# 2023.net
KiCad netlist of a schematic drawn in EAGLE
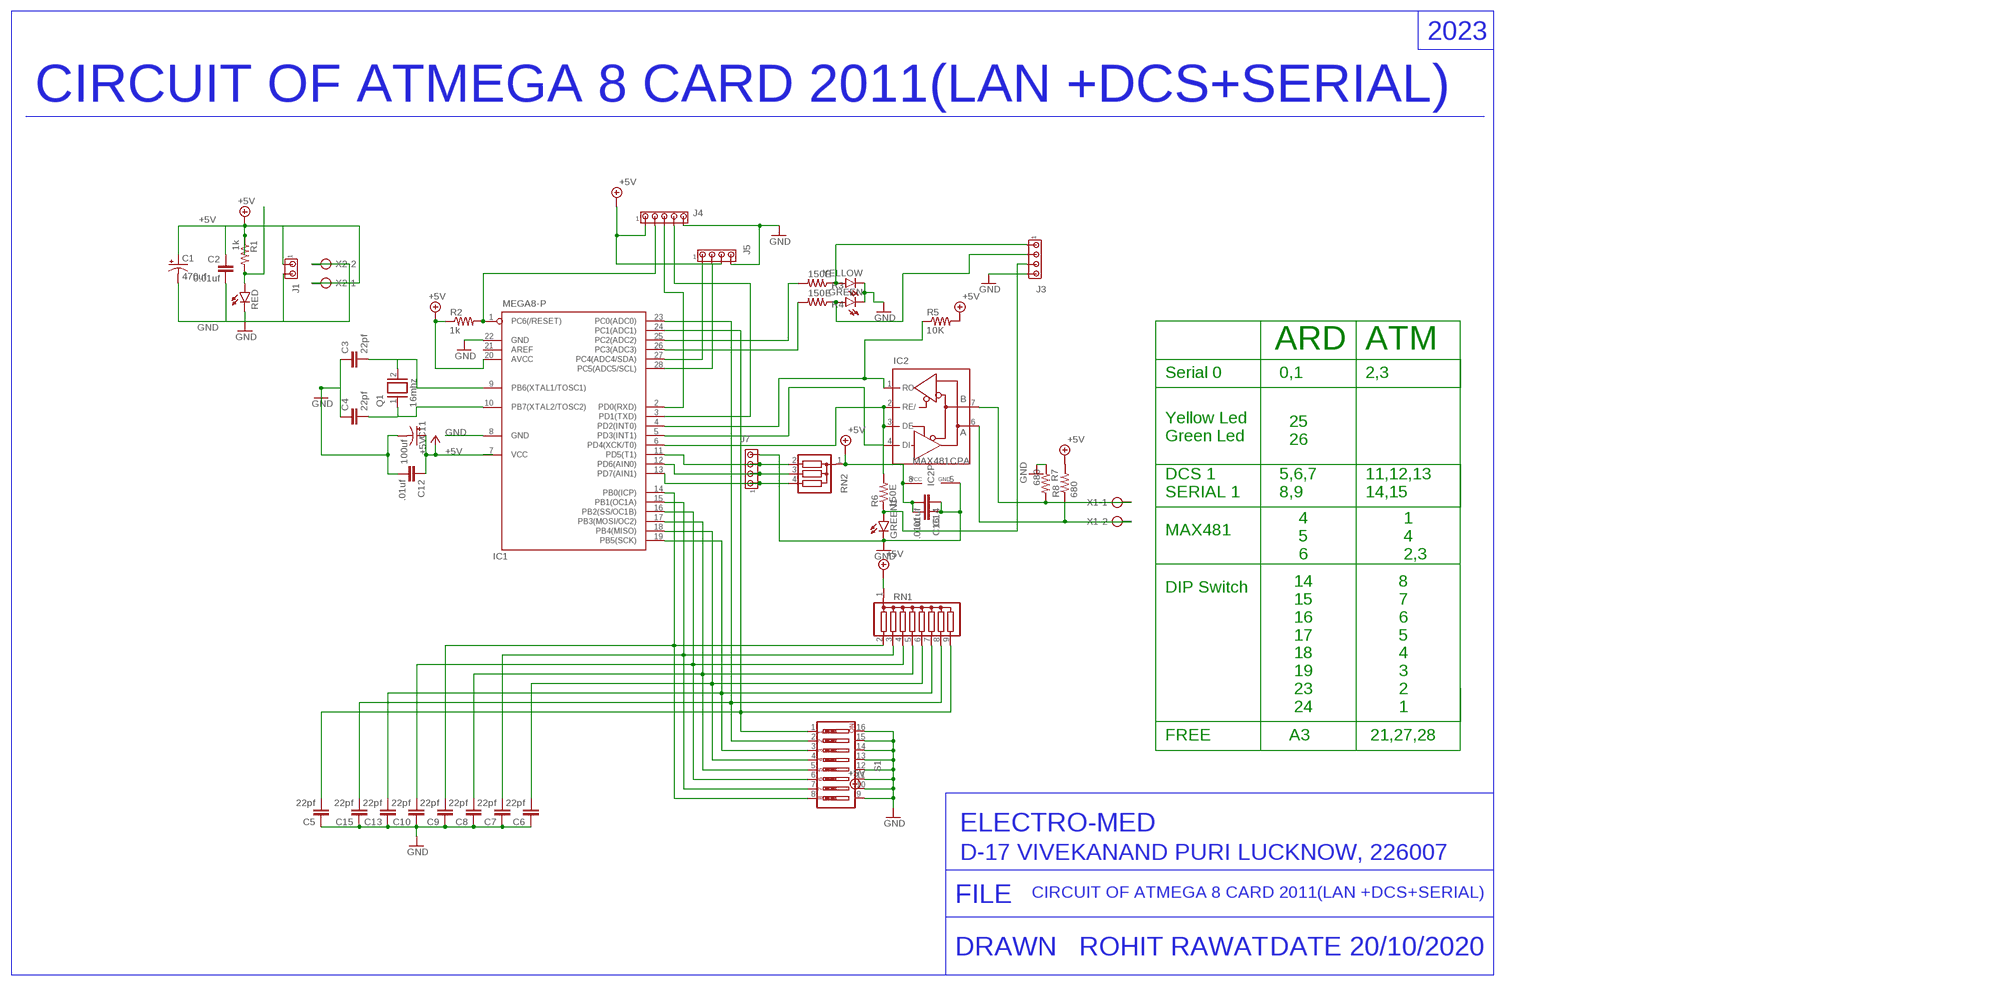
[diagram p0: schematic, sheet 1]

(export (version "E")
  (design (tool "Eeschema 10.0.6"))
  (components
    (comp (ref "C1")
      (value "470uf")
      (footprint "eagle-import:E5-10,5")
      (libsource (lib "eagle-import") (part "CPOL-USE5-10.5"))
    )
    (comp (ref "C2")
      (value "0.01uf")
      (footprint "eagle-import:C050-030X075")
      (libsource (lib "eagle-import") (part "C-EU-2050-030X075"))
    )
    (comp (ref "C3")
      (value "22pf")
      (footprint "eagle-import:C050-030X075")
      (libsource (lib "eagle-import") (part "C-EU-2050-030X075"))
    )
    (comp (ref "C4")
      (value "22pf")
      (footprint "eagle-import:C050-030X075")
      (libsource (lib "eagle-import") (part "C-EU-2050-030X075"))
    )
    (comp (ref "C5")
      (value "22pf")
      (footprint "eagle-import:C050-030X075")
      (libsource (lib "eagle-import") (part "C-EU-2050-030X075"))
    )
    (comp (ref "C6")
      (value "22pf")
      (footprint "eagle-import:C050-030X075")
      (libsource (lib "eagle-import") (part "C-EU-2050-030X075"))
    )
    (comp (ref "C7")
      (value "22pf")
      (footprint "eagle-import:C050-030X075")
      (libsource (lib "eagle-import") (part "C-EU-2050-030X075"))
    )
    (comp (ref "C8")
      (value "22pf")
      (footprint "eagle-import:C050-030X075")
      (libsource (lib "eagle-import") (part "C-EU-2050-030X075"))
    )
    (comp (ref "C9")
      (value "22pf")
      (footprint "eagle-import:C050-030X075")
      (libsource (lib "eagle-import") (part "C-EU-2050-030X075"))
    )
    (comp (ref "C10")
      (value "22pf")
      (footprint "eagle-import:C050-030X075")
      (libsource (lib "eagle-import") (part "C-EU-2050-030X075"))
    )
    (comp (ref "C11")
      (value "100uf")
      (footprint "eagle-import:E5-8,5")
      (libsource (lib "eagle-import") (part "rcl_334_CPOL-USE5-8.5"))
    )
    (comp (ref "C12")
      (value ".01uf")
      (footprint "eagle-import:C050-025X075")
      (libsource (lib "eagle-import") (part "C-EU050-025X075"))
    )
    (comp (ref "C13")
      (value "22pf")
      (footprint "eagle-import:C050-030X075")
      (libsource (lib "eagle-import") (part "C-EU-2050-030X075"))
    )
    (comp (ref "C14")
      (value ".01uf")
      (footprint "eagle-import:C050-025X075")
      (libsource (lib "eagle-import") (part "C-EU050-025X075"))
    )
    (comp (ref "C15")
      (value "22pf")
      (footprint "eagle-import:C050-030X075")
      (libsource (lib "eagle-import") (part "C-EU-2050-030X075"))
    )
    (comp (ref "C16")
      (value ".01uf")
      (footprint "eagle-import:C050-025X075")
      (libsource (lib "eagle-import") (part "C-EU050-025X075"))
    )
    (comp (ref "GREEN")
      (value "LED5MM")
      (footprint "eagle-import:LED5MM")
      (libsource (lib "eagle-import") (part "LED5MM"))
    )
    (comp (ref "GREEN1")
      (value "LED5MM")
      (footprint "eagle-import:LED5MM")
      (libsource (lib "eagle-import") (part "LED5MM"))
    )
    (comp (ref "IC1")
      (value "MEGA8-P")
      (footprint "eagle-import:DIL28-3")
      (libsource (lib "eagle-import") (part "MEGA8-P"))
    )
    (comp (ref "IC2")
      (value "MAX481CPA")
      (footprint "eagle-import:DIL08")
      (fields (field (name "MPN") "MAX481CPA+"))
      (libsource (lib "eagle-import") (part "MAX481CPA"))
    )
    (comp (ref "J1")
      (value "MTA02-100")
      (footprint "eagle-import:10X02MTA")
      (fields (field (name "SPICEPREFIX") "B"))
      (libsource (lib "eagle-import") (part "MTA02-100"))
    )
    (comp (ref "J3")
      (value "MTA04-100")
      (footprint "eagle-import:10X04MTA")
      (libsource (lib "eagle-import") (part "MTA04-100"))
    )
    (comp (ref "J4")
      (value "MTA05-100")
      (footprint "eagle-import:10X05MTA")
      (libsource (lib "eagle-import") (part "MTA05-100"))
    )
    (comp (ref "J5")
      (value "MTA04-100")
      (footprint "eagle-import:10X04MTA")
      (libsource (lib "eagle-import") (part "MTA04-100"))
    )
    (comp (ref "J7")
      (value "MTA04-100")
      (footprint "eagle-import:10X04MTA")
      (libsource (lib "eagle-import") (part "MTA04-100"))
    )
    (comp (ref "Q1")
      (value "16mhz")
      (footprint "eagle-import:QS")
      (libsource (lib "eagle-import") (part "XTAL/S"))
    )
    (comp (ref "R1")
      (value "1k")
      (footprint "eagle-import:0207_10")
      (libsource (lib "eagle-import") (part "R-US_0207/10"))
    )
    (comp (ref "R2")
      (value "1k")
      (footprint "eagle-import:0207_10")
      (libsource (lib "eagle-import") (part "R-US_0207/10"))
    )
    (comp (ref "R3")
      (value "150E")
      (footprint "eagle-import:0207_10")
      (libsource (lib "eagle-import") (part "R-US_0207/10"))
    )
    (comp (ref "R4")
      (value "150E")
      (footprint "eagle-import:0207_10")
      (libsource (lib "eagle-import") (part "R-US_0207/10"))
    )
    (comp (ref "R5")
      (value "10K")
      (footprint "eagle-import:0207_10")
      (libsource (lib "eagle-import") (part "R-US_0207/10"))
    )
    (comp (ref "R6")
      (value "150E")
      (footprint "eagle-import:0207_10")
      (libsource (lib "eagle-import") (part "R-US_0207/10"))
    )
    (comp (ref "R7")
      (value "680")
      (footprint "eagle-import:0207_10")
      (libsource (lib "eagle-import") (part "R-US_0207/10"))
    )
    (comp (ref "R8")
      (value "680")
      (footprint "eagle-import:0207_10")
      (libsource (lib "eagle-import") (part "R-US_0207/10"))
    )
    (comp (ref "RED")
      (value "LED5MM")
      (footprint "eagle-import:LED5MM")
      (libsource (lib "eagle-import") (part "LED5MM"))
    )
    (comp (ref "RN1")
      (value "G08R")
      (footprint "eagle-import:SIL9")
      (libsource (lib "eagle-import") (part "G08R"))
    )
    (comp (ref "RN2")
      (value "G03R")
      (footprint "eagle-import:SIL4")
      (libsource (lib "eagle-import") (part "G03R"))
    )
    (comp (ref "S1")
      (value "SW_DIP-8")
      (footprint "eagle-import:EDG-08")
      (libsource (lib "eagle-import") (part "SW_DIP-8"))
    )
    (comp (ref "X1")
      (value "AK300/2")
      (footprint "eagle-import:AK300_2")
      (libsource (lib "eagle-import") (part "AK300/2"))
    )
    (comp (ref "X2")
      (value "AK300/2")
      (footprint "eagle-import:AK300_2")
      (libsource (lib "eagle-import") (part "em con-ptr500_AK300/2"))
    )
    (comp (ref "YELLOW")
      (value "LED5MM")
      (footprint "eagle-import:LED5MM")
      (libsource (lib "eagle-import") (part "LED5MM"))
    )
  )
  (nets
    (net (code "1") (name "+5V") (class "Default")
      (node (ref "C1") (pin "+") (pinfunction "+_+") (pintype "passive"))
      (node (ref "C11") (pin "+") (pinfunction "+_+") (pintype "passive"))
      (node (ref "C12") (pin "1") (pinfunction "1_1") (pintype "passive"))
      (node (ref "C14") (pin "2") (pinfunction "2_2") (pintype "passive"))
      (node (ref "C16") (pin "2") (pinfunction "2_2") (pintype "passive"))
      (node (ref "C2") (pin "1") (pinfunction "1_1") (pintype "passive"))
      (node (ref "IC1") (pin "20") (pinfunction "AVCC_20") (pintype "power_in"))
      (node (ref "IC1") (pin "7") (pinfunction "VCC_7") (pintype "power_in"))
      (node (ref "IC2") (pin "8") (pinfunction "VCC_8") (pintype "power_in"))
      (node (ref "J1") (pin "1") (pinfunction "1_1") (pintype "passive"))
      (node (ref "J4") (pin "1") (pinfunction "1_1") (pintype "passive"))
      (node (ref "J5") (pin "3") (pinfunction "3_3") (pintype "passive"))
      (node (ref "R1") (pin "1") (pinfunction "1_1") (pintype "passive"))
      (node (ref "R2") (pin "1") (pinfunction "1_1") (pintype "passive"))
      (node (ref "R5") (pin "2") (pinfunction "2_2") (pintype "passive"))
      (node (ref "R8") (pin "2") (pinfunction "2_2") (pintype "passive"))
      (node (ref "RN1") (pin "1") (pinfunction "1_1") (pintype "passive"))
      (node (ref "RN2") (pin "1") (pinfunction "1_1") (pintype "passive"))
      (node (ref "X2") (pin "1") (pinfunction "KL_1") (pintype "passive"))
    )
    (net (code "2") (name "GND") (class "Default")
      (node (ref "C1") (pin "-") (pinfunction "-_-") (pintype "passive"))
      (node (ref "C10") (pin "1") (pinfunction "1_1") (pintype "passive"))
      (node (ref "C11") (pin "-") (pinfunction "-_-") (pintype "passive"))
      (node (ref "C12") (pin "2") (pinfunction "2_2") (pintype "passive"))
      (node (ref "C13") (pin "1") (pinfunction "1_1") (pintype "passive"))
      (node (ref "C14") (pin "1") (pinfunction "1_1") (pintype "passive"))
      (node (ref "C15") (pin "1") (pinfunction "1_1") (pintype "passive"))
      (node (ref "C16") (pin "1") (pinfunction "1_1") (pintype "passive"))
      (node (ref "C2") (pin "2") (pinfunction "2_2") (pintype "passive"))
      (node (ref "C3") (pin "1") (pinfunction "1_1") (pintype "passive"))
      (node (ref "C4") (pin "1") (pinfunction "1_1") (pintype "passive"))
      (node (ref "C5") (pin "1") (pinfunction "1_1") (pintype "passive"))
      (node (ref "C6") (pin "1") (pinfunction "1_1") (pintype "passive"))
      (node (ref "C7") (pin "1") (pinfunction "1_1") (pintype "passive"))
      (node (ref "C8") (pin "1") (pinfunction "1_1") (pintype "passive"))
      (node (ref "C9") (pin "1") (pinfunction "1_1") (pintype "passive"))
      (node (ref "GREEN") (pin "K") (pinfunction "C_K") (pintype "passive"))
      (node (ref "GREEN1") (pin "K") (pinfunction "C_K") (pintype "passive"))
      (node (ref "IC1") (pin "22") (pinfunction "GND_22") (pintype "power_in"))
      (node (ref "IC1") (pin "8") (pinfunction "GND_8") (pintype "power_in"))
      (node (ref "IC2") (pin "5") (pinfunction "GND_5") (pintype "power_in"))
      (node (ref "J1") (pin "2") (pinfunction "2_2") (pintype "passive"))
      (node (ref "J3") (pin "4") (pinfunction "4_4") (pintype "passive"))
      (node (ref "J4") (pin "5") (pinfunction "5_5") (pintype "passive"))
      (node (ref "J5") (pin "4") (pinfunction "4_4") (pintype "passive"))
      (node (ref "J7") (pin "4") (pinfunction "4_4") (pintype "passive"))
      (node (ref "R7") (pin "1") (pinfunction "1_1") (pintype "passive"))
      (node (ref "RED") (pin "K") (pinfunction "C_K") (pintype "passive"))
      (node (ref "S1") (pin "10") (pinfunction "10_10") (pintype "passive"))
      (node (ref "S1") (pin "11") (pinfunction "11_11") (pintype "passive"))
      (node (ref "S1") (pin "12") (pinfunction "12_12") (pintype "passive"))
      (node (ref "S1") (pin "13") (pinfunction "13_13") (pintype "passive"))
      (node (ref "S1") (pin "14") (pinfunction "14_14") (pintype "passive"))
      (node (ref "S1") (pin "15") (pinfunction "15_15") (pintype "passive"))
      (node (ref "S1") (pin "16") (pinfunction "16_16") (pintype "passive"))
      (node (ref "S1") (pin "9") (pinfunction "9_9") (pintype "passive"))
      (node (ref "X2") (pin "2") (pinfunction "KL_2") (pintype "passive"))
      (node (ref "YELLOW") (pin "K") (pinfunction "C_K") (pintype "passive"))
    )
    (net (code "3") (name "Net-(GREEN-PadA)") (class "Default")
      (node (ref "GREEN") (pin "A") (pinfunction "A_A") (pintype "passive"))
      (node (ref "J3") (pin "2") (pinfunction "2_2") (pintype "passive"))
      (node (ref "R4") (pin "1") (pinfunction "1_1") (pintype "passive"))
    )
    (net (code "4") (name "Net-(GREEN1-PadA)") (class "Default")
      (node (ref "GREEN1") (pin "A") (pinfunction "A_A") (pintype "passive"))
      (node (ref "J3") (pin "3") (pinfunction "3_3") (pintype "passive"))
      (node (ref "R6") (pin "1") (pinfunction "1_1") (pintype "passive"))
    )
    (net (code "5") (name "Net-(IC1-PB0(ICP))") (class "Default")
      (node (ref "C9") (pin "2") (pinfunction "2_2") (pintype "passive"))
      (node (ref "IC1") (pin "14") (pinfunction "PB0(ICP)_14") (pintype "bidirectional"))
      (node (ref "RN1") (pin "2") (pinfunction "2_2") (pintype "passive"))
      (node (ref "S1") (pin "8") (pinfunction "8_8") (pintype "passive"))
    )
    (net (code "6") (name "Net-(IC1-PB1(OC1A))") (class "Default")
      (node (ref "C7") (pin "2") (pinfunction "2_2") (pintype "passive"))
      (node (ref "IC1") (pin "15") (pinfunction "PB1(OC1A)_15") (pintype "bidirectional"))
      (node (ref "RN1") (pin "3") (pinfunction "3_3") (pintype "passive"))
      (node (ref "S1") (pin "7") (pinfunction "7_7") (pintype "passive"))
    )
    (net (code "7") (name "Net-(IC1-PB2(SS{slash}OC1B))") (class "Default")
      (node (ref "C10") (pin "2") (pinfunction "2_2") (pintype "passive"))
      (node (ref "IC1") (pin "16") (pinfunction "PB2(SS/OC1B)_16") (pintype "bidirectional"))
      (node (ref "RN1") (pin "4") (pinfunction "4_4") (pintype "passive"))
      (node (ref "S1") (pin "6") (pinfunction "6_6") (pintype "passive"))
    )
    (net (code "8") (name "Net-(IC1-PB3(MOSI{slash}OC2))") (class "Default")
      (node (ref "C8") (pin "2") (pinfunction "2_2") (pintype "passive"))
      (node (ref "IC1") (pin "17") (pinfunction "PB3(MOSI/OC2)_17") (pintype "bidirectional"))
      (node (ref "RN1") (pin "5") (pinfunction "5_5") (pintype "passive"))
      (node (ref "S1") (pin "5") (pinfunction "5_5") (pintype "passive"))
    )
    (net (code "9") (name "Net-(IC1-PB4(MISO))") (class "Default")
      (node (ref "C6") (pin "2") (pinfunction "2_2") (pintype "passive"))
      (node (ref "IC1") (pin "18") (pinfunction "PB4(MISO)_18") (pintype "bidirectional"))
      (node (ref "RN1") (pin "6") (pinfunction "6_6") (pintype "passive"))
      (node (ref "S1") (pin "4") (pinfunction "4_4") (pintype "passive"))
    )
    (net (code "10") (name "Net-(IC1-PB5(SCK))") (class "Default")
      (node (ref "C13") (pin "2") (pinfunction "2_2") (pintype "passive"))
      (node (ref "IC1") (pin "19") (pinfunction "PB5(SCK)_19") (pintype "bidirectional"))
      (node (ref "RN1") (pin "7") (pinfunction "7_7") (pintype "passive"))
      (node (ref "S1") (pin "3") (pinfunction "3_3") (pintype "passive"))
    )
    (net (code "11") (name "Net-(IC1-PB6(XTAL1{slash}TOSC1))") (class "Default")
      (node (ref "C3") (pin "2") (pinfunction "2_2") (pintype "passive"))
      (node (ref "IC1") (pin "9") (pinfunction "PB6(XTAL1/TOSC1)_9") (pintype "bidirectional"))
      (node (ref "Q1") (pin "2") (pinfunction "2_2") (pintype "passive"))
    )
    (net (code "12") (name "Net-(IC1-PB7(XTAL2{slash}TOSC2))") (class "Default")
      (node (ref "C4") (pin "2") (pinfunction "2_2") (pintype "passive"))
      (node (ref "IC1") (pin "10") (pinfunction "PB7(XTAL2/TOSC2)_10") (pintype "bidirectional"))
      (node (ref "Q1") (pin "1") (pinfunction "1_1") (pintype "passive"))
    )
    (net (code "13") (name "Net-(IC1-PC0(ADC0))") (class "Default")
      (node (ref "C15") (pin "2") (pinfunction "2_2") (pintype "passive"))
      (node (ref "IC1") (pin "23") (pinfunction "PC0(ADC0)_23") (pintype "bidirectional"))
      (node (ref "RN1") (pin "8") (pinfunction "8_8") (pintype "passive"))
      (node (ref "S1") (pin "2") (pinfunction "2_2") (pintype "passive"))
    )
    (net (code "14") (name "Net-(IC1-PC1(ADC1))") (class "Default")
      (node (ref "C5") (pin "2") (pinfunction "2_2") (pintype "passive"))
      (node (ref "IC1") (pin "24") (pinfunction "PC1(ADC1)_24") (pintype "bidirectional"))
      (node (ref "RN1") (pin "9") (pinfunction "9_9") (pintype "passive"))
      (node (ref "S1") (pin "1") (pinfunction "1_1") (pintype "passive"))
    )
    (net (code "15") (name "Net-(IC1-PC2(ADC2))") (class "Default")
      (node (ref "IC1") (pin "25") (pinfunction "PC2(ADC2)_25") (pintype "bidirectional"))
      (node (ref "R3") (pin "2") (pinfunction "2_2") (pintype "passive"))
    )
    (net (code "16") (name "Net-(IC1-PC3(ADC3))") (class "Default")
      (node (ref "IC1") (pin "26") (pinfunction "PC3(ADC3)_26") (pintype "bidirectional"))
      (node (ref "R4") (pin "2") (pinfunction "2_2") (pintype "passive"))
    )
    (net (code "17") (name "Net-(IC1-PC4(ADC4{slash}SDA))") (class "Default")
      (node (ref "IC1") (pin "27") (pinfunction "PC4(ADC4/SDA)_27") (pintype "bidirectional"))
      (node (ref "J5") (pin "1") (pinfunction "1_1") (pintype "passive"))
    )
    (net (code "18") (name "Net-(IC1-PC5(ADC5{slash}SCL))") (class "Default")
      (node (ref "IC1") (pin "28") (pinfunction "PC5(ADC5/SCL)_28") (pintype "bidirectional"))
      (node (ref "J5") (pin "2") (pinfunction "2_2") (pintype "passive"))
    )
    (net (code "19") (name "Net-(IC1-PC6({slash}RESET))") (class "Default")
      (node (ref "IC1") (pin "1") (pinfunction "PC6(/RESET)_1") (pintype "bidirectional"))
      (node (ref "J4") (pin "2") (pinfunction "2_2") (pintype "passive"))
      (node (ref "R2") (pin "2") (pinfunction "2_2") (pintype "passive"))
    )
    (net (code "20") (name "Net-(IC1-PD0(RXD))") (class "Default")
      (node (ref "IC1") (pin "2") (pinfunction "PD0(RXD)_2") (pintype "bidirectional"))
      (node (ref "J4") (pin "3") (pinfunction "3_3") (pintype "passive"))
    )
    (net (code "21") (name "Net-(IC1-PD1(TXD))") (class "Default")
      (node (ref "IC1") (pin "3") (pinfunction "PD1(TXD)_3") (pintype "bidirectional"))
      (node (ref "J4") (pin "4") (pinfunction "4_4") (pintype "passive"))
    )
    (net (code "22") (name "Net-(IC1-PD2(INT0))") (class "Default")
      (node (ref "IC1") (pin "4") (pinfunction "PD2(INT0)_4") (pintype "bidirectional"))
      (node (ref "IC2") (pin "1") (pinfunction "RO_1") (pintype "output"))
      (node (ref "R5") (pin "1") (pinfunction "1_1") (pintype "passive"))
    )
    (net (code "23") (name "Net-(IC1-PD3(INT1))") (class "Default")
      (node (ref "IC1") (pin "5") (pinfunction "PD3(INT1)_5") (pintype "bidirectional"))
      (node (ref "IC2") (pin "4") (pinfunction "DI_4") (pintype "input"))
    )
    (net (code "24") (name "Net-(IC1-PD4(XCK{slash}T0))") (class "Default")
      (node (ref "IC1") (pin "6") (pinfunction "PD4(XCK/T0)_6") (pintype "bidirectional"))
      (node (ref "IC2") (pin "2") (pinfunction "RE/_2") (pintype "input"))
      (node (ref "IC2") (pin "3") (pinfunction "DE_3") (pintype "input"))
      (node (ref "R6") (pin "2") (pinfunction "2_2") (pintype "passive"))
    )
    (net (code "25") (name "Net-(IC1-PD5(T1))") (class "Default")
      (node (ref "IC1") (pin "11") (pinfunction "PD5(T1)_11") (pintype "bidirectional"))
      (node (ref "J7") (pin "3") (pinfunction "3_3") (pintype "passive"))
      (node (ref "RN2") (pin "2") (pinfunction "2_2") (pintype "passive"))
    )
    (net (code "26") (name "Net-(IC1-PD6(AIN0))") (class "Default")
      (node (ref "IC1") (pin "12") (pinfunction "PD6(AIN0)_12") (pintype "bidirectional"))
      (node (ref "J7") (pin "2") (pinfunction "2_2") (pintype "passive"))
      (node (ref "RN2") (pin "3") (pinfunction "3_3") (pintype "passive"))
    )
    (net (code "27") (name "Net-(IC1-PD7(AIN1))") (class "Default")
      (node (ref "IC1") (pin "13") (pinfunction "PD7(AIN1)_13") (pintype "bidirectional"))
      (node (ref "J7") (pin "1") (pinfunction "1_1") (pintype "passive"))
      (node (ref "RN2") (pin "4") (pinfunction "4_4") (pintype "passive"))
    )
    (net (code "28") (name "Net-(IC2A-A)") (class "Default")
      (node (ref "IC2") (pin "6") (pinfunction "A_6") (pintype "passive"))
      (node (ref "R8") (pin "1") (pinfunction "1_1") (pintype "passive"))
      (node (ref "X1") (pin "2") (pinfunction "KL_2") (pintype "passive"))
    )
    (net (code "29") (name "Net-(IC2A-B)") (class "Default")
      (node (ref "IC2") (pin "7") (pinfunction "B_7") (pintype "passive"))
      (node (ref "R7") (pin "2") (pinfunction "2_2") (pintype "passive"))
      (node (ref "X1") (pin "1") (pinfunction "KL_1") (pintype "passive"))
    )
    (net (code "30") (name "Net-(J3-Pad1)") (class "Default")
      (node (ref "J3") (pin "1") (pinfunction "1_1") (pintype "passive"))
      (node (ref "R3") (pin "1") (pinfunction "1_1") (pintype "passive"))
      (node (ref "YELLOW") (pin "A") (pinfunction "A_A") (pintype "passive"))
    )
    (net (code "31") (name "Net-(R1-Pad2)") (class "Default")
      (node (ref "R1") (pin "2") (pinfunction "2_2") (pintype "passive"))
      (node (ref "RED") (pin "A") (pinfunction "A_A") (pintype "passive"))
    )
    (net (code "32") (name "unconnected-(IC1-AREF-Pad21)") (class "Default")
      (node (ref "IC1") (pin "21") (pinfunction "AREF_21") (pintype "passive"))
    )
  )
)
